# energia.net
KiCad netlist of a schematic drawn in EAGLE
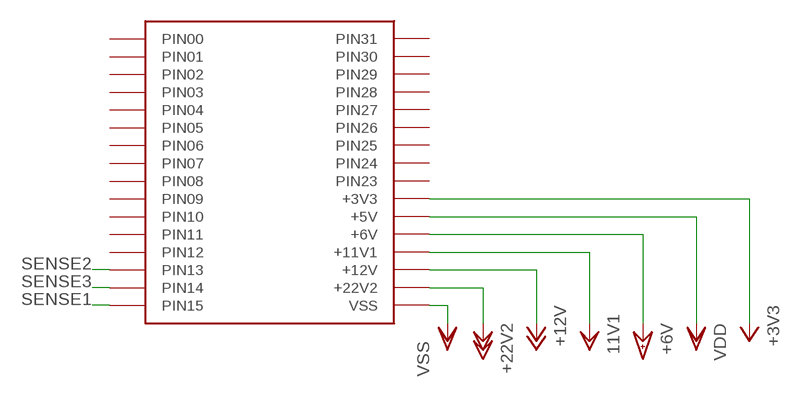
[diagram p0: schematic, sheet 1]
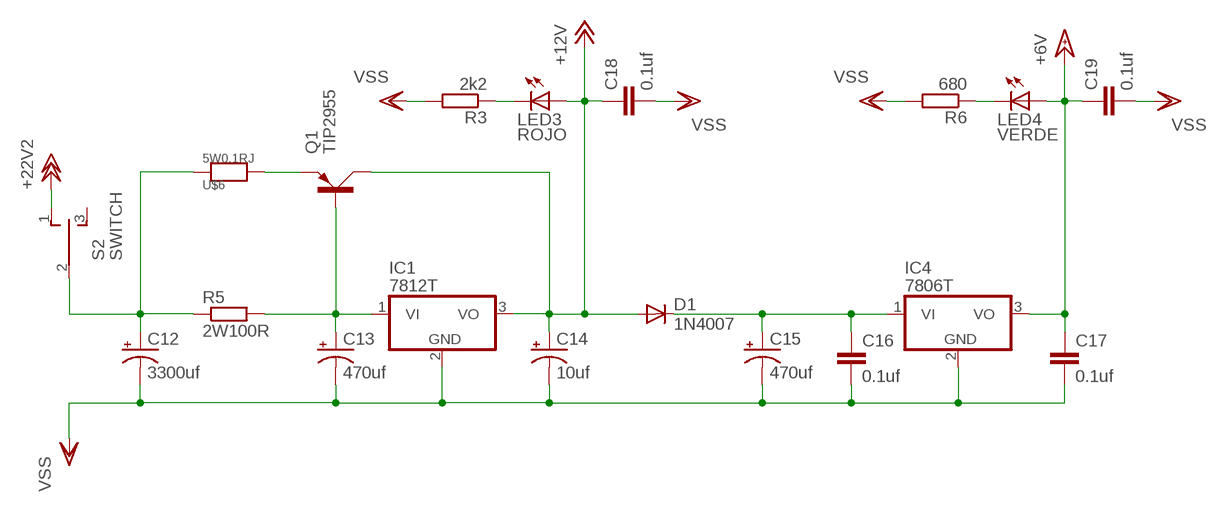
[diagram p1: schematic, sheet 2]
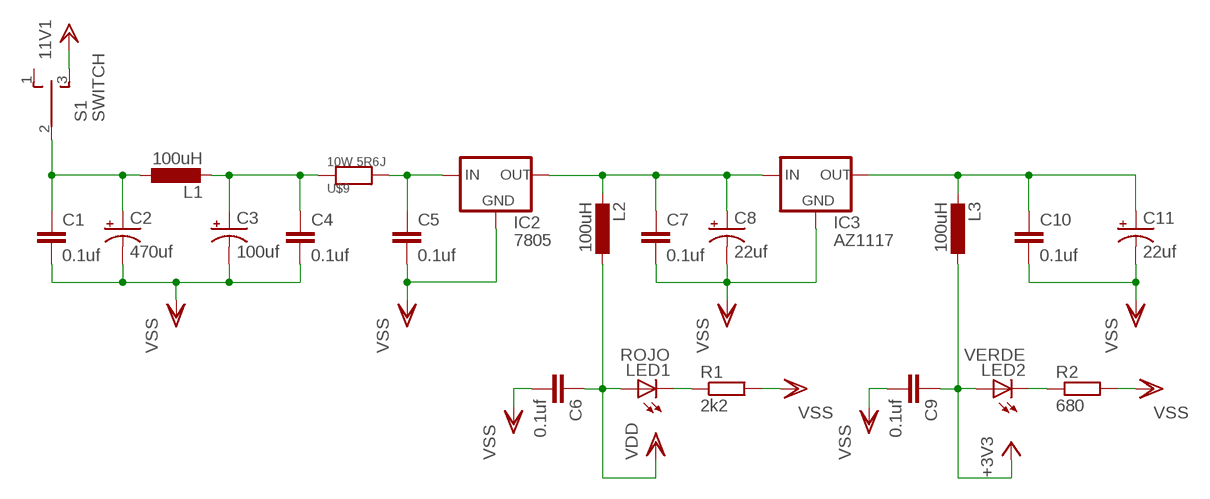
[diagram p2: schematic, sheet 3]
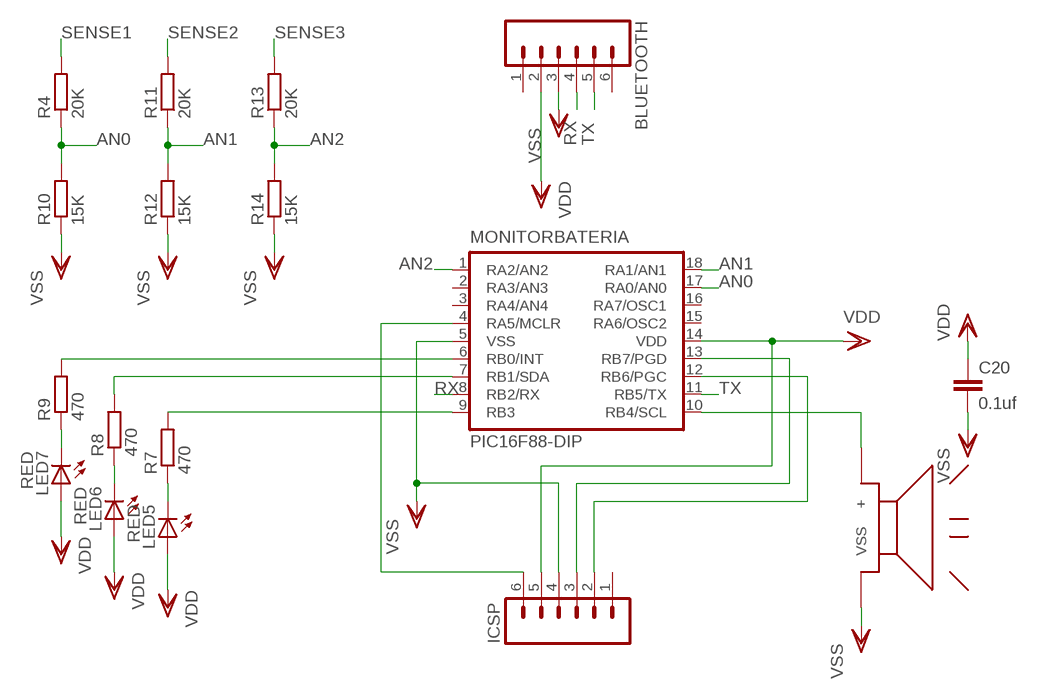
[diagram p3: schematic, sheet 4]

(export (version "E")
  (design (tool "Eeschema 10.0.6"))
  (components
    (comp (ref "BLUETOOTH")
      (value "M06LONGPADS")
      (footprint "eagle-import:1X06_LONGPADS")
      (libsource (lib "eagle-import") (part "M06LONGPADS"))
    )
    (comp (ref "C20")
      (value "0.1uf")
      (footprint "eagle-import:C050-024X044")
      (libsource (lib "eagle-import") (part "C-EU050-024X044"))
    )
    (comp (ref "ICSP")
      (value "M06LONGPADS")
      (footprint "eagle-import:1X06_LONGPADS")
      (libsource (lib "eagle-import") (part "M06LONGPADS"))
    )
    (comp (ref "LED5")
      (value "RED")
      (footprint "eagle-import:LED3MM")
      (libsource (lib "eagle-import") (part "LED3MM"))
    )
    (comp (ref "LED6")
      (value "RED")
      (footprint "eagle-import:LED3MM")
      (libsource (lib "eagle-import") (part "LED3MM"))
    )
    (comp (ref "LED7")
      (value "RED")
      (footprint "eagle-import:LED3MM")
      (libsource (lib "eagle-import") (part "LED3MM"))
    )
    (comp (ref "MONITORBATERIA")
      (value "PIC16F88-DIP")
      (footprint "eagle-import:DIL18")
      (libsource (lib "eagle-import") (part "PIC16F88-DIP"))
    )
    (comp (ref "R4")
      (value "20K")
      (footprint "eagle-import:0204_5")
      (libsource (lib "eagle-import") (part "R-EU_0204/5"))
    )
    (comp (ref "R7")
      (value "470")
      (footprint "eagle-import:0204_5")
      (libsource (lib "eagle-import") (part "R-EU_0204/5"))
    )
    (comp (ref "R8")
      (value "470")
      (footprint "eagle-import:0204_5")
      (libsource (lib "eagle-import") (part "R-EU_0204/5"))
    )
    (comp (ref "R9")
      (value "470")
      (footprint "eagle-import:0204_5")
      (libsource (lib "eagle-import") (part "R-EU_0204/5"))
    )
    (comp (ref "R10")
      (value "15K")
      (footprint "eagle-import:0204_5")
      (libsource (lib "eagle-import") (part "R-EU_0204/5"))
    )
    (comp (ref "R11")
      (value "20K")
      (footprint "eagle-import:0204_5")
      (libsource (lib "eagle-import") (part "R-EU_0204/5"))
    )
    (comp (ref "R12")
      (value "15K")
      (footprint "eagle-import:0204_5")
      (libsource (lib "eagle-import") (part "R-EU_0204/5"))
    )
    (comp (ref "R13")
      (value "20K")
      (footprint "eagle-import:0204_5")
      (libsource (lib "eagle-import") (part "R-EU_0204/5"))
    )
    (comp (ref "R14")
      (value "15K")
      (footprint "eagle-import:0204_5")
      (libsource (lib "eagle-import") (part "R-EU_0204/5"))
    )
    (comp (ref "U$10")
      (value "BUZZER")
      (footprint "eagle-import:BUZZER")
      (libsource (lib "eagle-import") (part "BUZZER"))
    )
    (comp (ref "C12")
      (value "3300uf")
      (footprint "eagle-import:E7,5-18")
      (libsource (lib "eagle-import") (part "CPOL-USE7.5-18"))
    )
    (comp (ref "C13")
      (value "470uf")
      (footprint "eagle-import:E3,5-8")
      (libsource (lib "eagle-import") (part "CPOL-USE3.5-8"))
    )
    (comp (ref "C14")
      (value "10uf")
      (footprint "eagle-import:E2,5-5")
      (libsource (lib "eagle-import") (part "CPOL-USE2.5-5"))
    )
    (comp (ref "C15")
      (value "470uf")
      (footprint "eagle-import:E3,5-8")
      (libsource (lib "eagle-import") (part "CPOL-USE3.5-8"))
    )
    (comp (ref "C16")
      (value "0.1uf")
      (footprint "eagle-import:C050-024X044")
      (libsource (lib "eagle-import") (part "C-EU050-024X044"))
    )
    (comp (ref "C17")
      (value "0.1uf")
      (footprint "eagle-import:C050-024X044")
      (libsource (lib "eagle-import") (part "C-EU050-024X044"))
    )
    (comp (ref "C18")
      (value "0.1uf")
      (footprint "eagle-import:C050-024X044")
      (libsource (lib "eagle-import") (part "C-EU050-024X044"))
    )
    (comp (ref "C19")
      (value "0.1uf")
      (footprint "eagle-import:C050-024X044")
      (libsource (lib "eagle-import") (part "C-EU050-024X044"))
    )
    (comp (ref "D1")
      (value "1N4007")
      (footprint "eagle-import:DO41-10")
      (libsource (lib "eagle-import") (part "1N4004"))
    )
    (comp (ref "IC1")
      (value "7812T")
      (footprint "eagle-import:TO220H")
      (libsource (lib "eagle-import") (part "78T12"))
    )
    (comp (ref "IC4")
      (value "7806T")
      (footprint "eagle-import:TO220H")
      (libsource (lib "eagle-import") (part "78T06"))
    )
    (comp (ref "LED3")
      (value "ROJO")
      (footprint "eagle-import:LED3MM")
      (libsource (lib "eagle-import") (part "LED3MM"))
    )
    (comp (ref "LED4")
      (value "VERDE")
      (footprint "eagle-import:LED3MM")
      (libsource (lib "eagle-import") (part "LED3MM"))
    )
    (comp (ref "Q1")
      (value "TIP2955")
      (footprint "eagle-import:TOP3AV")
      (libsource (lib "eagle-import") (part "TIP2955"))
    )
    (comp (ref "R3")
      (value "2k2")
      (footprint "eagle-import:0204_5")
      (libsource (lib "eagle-import") (part "R-EU_0204/5"))
    )
    (comp (ref "R5")
      (value "2W100R")
      (footprint "eagle-import:0411_12")
      (libsource (lib "eagle-import") (part "R-EU_0411/12"))
    )
    (comp (ref "R6")
      (value "680")
      (footprint "eagle-import:0204_5")
      (libsource (lib "eagle-import") (part "R-EU_0204/5"))
    )
    (comp (ref "S2")
      (value "SWITCH")
      (footprint "eagle-import:TL3XYO")
      (libsource (lib "eagle-import") (part "TL39YOSWITCH_2_ESTADOS"))
    )
    (comp (ref "U$6")
      (value "5W0.1RJ")
      (footprint "eagle-import:RES-22X10")
      (libsource (lib "eagle-import") (part "RESISTENCIA5WATT"))
    )
    (comp (ref "C1")
      (value "0.1uf")
      (footprint "eagle-import:C050-024X044")
      (libsource (lib "eagle-import") (part "C-EU050-024X044"))
    )
    (comp (ref "C2")
      (value "470uf")
      (footprint "eagle-import:E2,5-7")
      (libsource (lib "eagle-import") (part "CPOL-USE2.5-7"))
    )
    (comp (ref "C3")
      (value "100uf")
      (footprint "eagle-import:E2,5-7")
      (libsource (lib "eagle-import") (part "CPOL-USE2.5-7"))
    )
    (comp (ref "C4")
      (value "0.1uf")
      (footprint "eagle-import:C050-024X044")
      (libsource (lib "eagle-import") (part "C-EU050-024X044"))
    )
    (comp (ref "C5")
      (value "0.1uf")
      (footprint "eagle-import:C050-024X044")
      (libsource (lib "eagle-import") (part "C-EU050-024X044"))
    )
    (comp (ref "C6")
      (value "0.1uf")
      (footprint "eagle-import:C050-024X044")
      (libsource (lib "eagle-import") (part "C-EU050-024X044"))
    )
    (comp (ref "C7")
      (value "0.1uf")
      (footprint "eagle-import:C050-024X044")
      (libsource (lib "eagle-import") (part "C-EU050-024X044"))
    )
    (comp (ref "C8")
      (value "22uf")
      (footprint "eagle-import:E2,5-7")
      (libsource (lib "eagle-import") (part "CPOL-USE2.5-7"))
    )
    (comp (ref "C9")
      (value "0.1uf")
      (footprint "eagle-import:C050-024X044")
      (libsource (lib "eagle-import") (part "C-EU050-024X044"))
    )
    (comp (ref "C10")
      (value "0.1uf")
      (footprint "eagle-import:C050-024X044")
      (libsource (lib "eagle-import") (part "C-EU050-024X044"))
    )
    (comp (ref "C11")
      (value "22uf")
      (footprint "eagle-import:E2,5-7")
      (libsource (lib "eagle-import") (part "CPOL-USE2.5-7"))
    )
    (comp (ref "IC2")
      (value "7805")
      (footprint "eagle-import:TO-220-ALT")
      (libsource (lib "eagle-import") (part "V_REG_78XX-TO-220"))
    )
    (comp (ref "IC3")
      (value "AZ1117")
      (footprint "eagle-import:78XXL")
      (libsource (lib "eagle-import") (part "V_REG_LD1117VXX"))
    )
    (comp (ref "L1")
      (value "100uH")
      (footprint "eagle-import:TFI0307")
      (libsource (lib "eagle-import") (part "L-EUTFI0307"))
    )
    (comp (ref "L2")
      (value "100uH")
      (footprint "eagle-import:0207_7")
      (libsource (lib "eagle-import") (part "L-EU0207/7"))
    )
    (comp (ref "L3")
      (value "100uH")
      (footprint "eagle-import:0207_7")
      (libsource (lib "eagle-import") (part "L-EU0207/7"))
    )
    (comp (ref "LED1")
      (value "ROJO")
      (footprint "eagle-import:LED3MM")
      (libsource (lib "eagle-import") (part "LED3MM"))
    )
    (comp (ref "LED2")
      (value "VERDE")
      (footprint "eagle-import:LED3MM")
      (libsource (lib "eagle-import") (part "LED3MM"))
    )
    (comp (ref "R1")
      (value "2k2")
      (footprint "eagle-import:0204_5")
      (libsource (lib "eagle-import") (part "R-EU_0204/5"))
    )
    (comp (ref "R2")
      (value "680")
      (footprint "eagle-import:0204_5")
      (libsource (lib "eagle-import") (part "R-EU_0204/5"))
    )
    (comp (ref "S1")
      (value "SWITCH")
      (footprint "eagle-import:TL3XYO")
      (libsource (lib "eagle-import") (part "TL39YOSWITCH_2_ESTADOS"))
    )
    (comp (ref "U$9")
      (value "10W 5R6J")
      (footprint "eagle-import:RES-49X10")
      (libsource (lib "eagle-import") (part "RESISTENCIA10W"))
    )
    (comp (ref "U$1")
      (value "BASE")
      (footprint "eagle-import:BASE")
      (libsource (lib "eagle-import") (part "BASE"))
    )
  )
  (nets
    (net (code "1") (name "+3V3") (class "Default")
      (node (ref "C9") (pin "1") (pinfunction "1_1") (pintype "passive"))
      (node (ref "L3") (pin "1") (pinfunction "1_1") (pintype "passive"))
      (node (ref "LED2") (pin "A") (pinfunction "A_A") (pintype "passive"))
      (node (ref "U$1") (pin "PIN22") (pinfunction "+3V3_PIN22") (pintype "bidirectional"))
    )
    (net (code "2") (name "+6V") (class "Default")
      (node (ref "C17") (pin "1") (pinfunction "1_1") (pintype "passive"))
      (node (ref "C19") (pin "1") (pinfunction "1_1") (pintype "passive"))
      (node (ref "IC4") (pin "3") (pinfunction "VO_3") (pintype "passive"))
      (node (ref "LED4") (pin "A") (pinfunction "A_A") (pintype "passive"))
      (node (ref "U$1") (pin "PIN20") (pinfunction "+6V_PIN20") (pintype "bidirectional"))
    )
    (net (code "3") (name "+11V1") (class "Default")
      (node (ref "S1") (pin "3") (pinfunction "S_3") (pintype "passive"))
      (node (ref "U$1") (pin "PIN19") (pinfunction "+11V1_PIN19") (pintype "bidirectional"))
    )
    (net (code "4") (name "+12V") (class "Default")
      (node (ref "C14") (pin "+") (pinfunction "+_+") (pintype "passive"))
      (node (ref "C18") (pin "1") (pinfunction "1_1") (pintype "passive"))
      (node (ref "D1") (pin "A") (pinfunction "A_A") (pintype "passive"))
      (node (ref "IC1") (pin "3") (pinfunction "VO_3") (pintype "passive"))
      (node (ref "LED3") (pin "A") (pinfunction "A_A") (pintype "passive"))
      (node (ref "Q1") (pin "C") (pinfunction "C_C") (pintype "passive"))
      (node (ref "U$1") (pin "PIN18") (pinfunction "+12V_PIN18") (pintype "bidirectional"))
    )
    (net (code "5") (name "+22V") (class "Default")
      (node (ref "S2") (pin "1") (pinfunction "O_1") (pintype "passive"))
      (node (ref "U$1") (pin "PIN17") (pinfunction "+22V2_PIN17") (pintype "bidirectional"))
    )
    (net (code "6") (name "AN0") (class "Default")
      (node (ref "MONITORBATERIA") (pin "17") (pinfunction "RA0/AN0_17") (pintype "bidirectional"))
      (node (ref "R10") (pin "2") (pinfunction "2_2") (pintype "passive"))
      (node (ref "R4") (pin "1") (pinfunction "1_1") (pintype "passive"))
    )
    (net (code "7") (name "AN1") (class "Default")
      (node (ref "MONITORBATERIA") (pin "18") (pinfunction "RA1/AN1_18") (pintype "bidirectional"))
      (node (ref "R11") (pin "1") (pinfunction "1_1") (pintype "passive"))
      (node (ref "R12") (pin "2") (pinfunction "2_2") (pintype "passive"))
    )
    (net (code "8") (name "AN2") (class "Default")
      (node (ref "MONITORBATERIA") (pin "1") (pinfunction "RA2/AN2_1") (pintype "bidirectional"))
      (node (ref "R13") (pin "1") (pinfunction "1_1") (pintype "passive"))
      (node (ref "R14") (pin "2") (pinfunction "2_2") (pintype "passive"))
    )
    (net (code "9") (name "Net-(C3-Pad+)") (class "Default")
      (node (ref "C3") (pin "+") (pinfunction "+_+") (pintype "passive"))
      (node (ref "C4") (pin "1") (pinfunction "1_1") (pintype "passive"))
      (node (ref "L1") (pin "2") (pinfunction "2_2") (pintype "passive"))
      (node (ref "U$9") (pin "P$1") (pinfunction "P$1_P$1") (pintype "bidirectional"))
    )
    (net (code "10") (name "Net-(C5-Pad1)") (class "Default")
      (node (ref "C5") (pin "1") (pinfunction "1_1") (pintype "passive"))
      (node (ref "IC2") (pin "IN") (pinfunction "IN_IN") (pintype "input"))
      (node (ref "U$9") (pin "P$2") (pinfunction "P$2_P$2") (pintype "bidirectional"))
    )
    (net (code "11") (name "Net-(IC1-VI)") (class "Default")
      (node (ref "C13") (pin "+") (pinfunction "+_+") (pintype "passive"))
      (node (ref "IC1") (pin "1") (pinfunction "VI_1") (pintype "input"))
      (node (ref "Q1") (pin "B") (pinfunction "B_B") (pintype "passive"))
      (node (ref "R5") (pin "2") (pinfunction "2_2") (pintype "passive"))
    )
    (net (code "12") (name "Net-(IC3-IN)") (class "Default")
      (node (ref "C7") (pin "1") (pinfunction "1_1") (pintype "passive"))
      (node (ref "C8") (pin "+") (pinfunction "+_+") (pintype "passive"))
      (node (ref "IC2") (pin "OUT") (pinfunction "OUT_OUT") (pintype "output"))
      (node (ref "IC3") (pin "OUT") (pinfunction "IN_OUT") (pintype "input"))
      (node (ref "L2") (pin "2") (pinfunction "2_2") (pintype "passive"))
    )
    (net (code "13") (name "Net-(IC3-OUT)") (class "Default")
      (node (ref "C10") (pin "1") (pinfunction "1_1") (pintype "passive"))
      (node (ref "C11") (pin "+") (pinfunction "+_+") (pintype "passive"))
      (node (ref "IC3") (pin "GND") (pinfunction "OUT_GND") (pintype "output"))
      (node (ref "L3") (pin "2") (pinfunction "2_2") (pintype "passive"))
    )
    (net (code "14") (name "Net-(IC4-VI)") (class "Default")
      (node (ref "C15") (pin "+") (pinfunction "+_+") (pintype "passive"))
      (node (ref "C16") (pin "1") (pinfunction "1_1") (pintype "passive"))
      (node (ref "D1") (pin "C") (pinfunction "C_C") (pintype "passive"))
      (node (ref "IC4") (pin "1") (pinfunction "VI_1") (pintype "input"))
    )
    (net (code "15") (name "Net-(LED1-C)") (class "Default")
      (node (ref "LED1") (pin "K") (pinfunction "C_K") (pintype "passive"))
      (node (ref "R1") (pin "1") (pinfunction "1_1") (pintype "passive"))
    )
    (net (code "16") (name "Net-(LED2-C)") (class "Default")
      (node (ref "LED2") (pin "K") (pinfunction "C_K") (pintype "passive"))
      (node (ref "R2") (pin "1") (pinfunction "1_1") (pintype "passive"))
    )
    (net (code "17") (name "Net-(LED3-C)") (class "Default")
      (node (ref "LED3") (pin "K") (pinfunction "C_K") (pintype "passive"))
      (node (ref "R3") (pin "1") (pinfunction "1_1") (pintype "passive"))
    )
    (net (code "18") (name "Net-(LED4-C)") (class "Default")
      (node (ref "LED4") (pin "K") (pinfunction "C_K") (pintype "passive"))
      (node (ref "R6") (pin "1") (pinfunction "1_1") (pintype "passive"))
    )
    (net (code "19") (name "Net-(LED5-C)") (class "Default")
      (node (ref "LED5") (pin "K") (pinfunction "C_K") (pintype "passive"))
      (node (ref "R7") (pin "1") (pinfunction "1_1") (pintype "passive"))
    )
    (net (code "20") (name "Net-(LED6-C)") (class "Default")
      (node (ref "LED6") (pin "K") (pinfunction "C_K") (pintype "passive"))
      (node (ref "R8") (pin "1") (pinfunction "1_1") (pintype "passive"))
    )
    (net (code "21") (name "Net-(LED7-C)") (class "Default")
      (node (ref "LED7") (pin "K") (pinfunction "C_K") (pintype "passive"))
      (node (ref "R9") (pin "1") (pinfunction "1_1") (pintype "passive"))
    )
    (net (code "22") (name "Net-(MONITORBATERIA-RA5{slash}MCLR)") (class "Default")
      (node (ref "ICSP") (pin "6") (pinfunction "6_6") (pintype "passive"))
      (node (ref "MONITORBATERIA") (pin "4") (pinfunction "RA5/MCLR_4") (pintype "input"))
    )
    (net (code "23") (name "Net-(MONITORBATERIA-RB0{slash}INT)") (class "Default")
      (node (ref "MONITORBATERIA") (pin "6") (pinfunction "RB0/INT_6") (pintype "bidirectional"))
      (node (ref "R9") (pin "2") (pinfunction "2_2") (pintype "passive"))
    )
    (net (code "24") (name "Net-(MONITORBATERIA-RB1{slash}SDA)") (class "Default")
      (node (ref "MONITORBATERIA") (pin "7") (pinfunction "RB1/SDA_7") (pintype "bidirectional"))
      (node (ref "R8") (pin "2") (pinfunction "2_2") (pintype "passive"))
    )
    (net (code "25") (name "Net-(MONITORBATERIA-RB3)") (class "Default")
      (node (ref "MONITORBATERIA") (pin "9") (pinfunction "RB3_9") (pintype "bidirectional"))
      (node (ref "R7") (pin "2") (pinfunction "2_2") (pintype "passive"))
    )
    (net (code "26") (name "Net-(MONITORBATERIA-RB4{slash}SCL)") (class "Default")
      (node (ref "MONITORBATERIA") (pin "10") (pinfunction "RB4/SCL_10") (pintype "bidirectional"))
      (node (ref "U$10") (pin "+") (pinfunction "+_+") (pintype "bidirectional"))
    )
    (net (code "27") (name "Net-(MONITORBATERIA-RB6{slash}PGC)") (class "Default")
      (node (ref "ICSP") (pin "2") (pinfunction "2_2") (pintype "passive"))
      (node (ref "MONITORBATERIA") (pin "12") (pinfunction "RB6/PGC_12") (pintype "bidirectional"))
    )
    (net (code "28") (name "Net-(MONITORBATERIA-RB7{slash}PGD)") (class "Default")
      (node (ref "ICSP") (pin "3") (pinfunction "3_3") (pintype "passive"))
      (node (ref "MONITORBATERIA") (pin "13") (pinfunction "RB7/PGD_13") (pintype "bidirectional"))
    )
    (net (code "29") (name "Net-(Q1-PadE)") (class "Default")
      (node (ref "Q1") (pin "E") (pinfunction "E_E") (pintype "passive"))
      (node (ref "U$6") (pin "P$2") (pinfunction "P$2_P$2") (pintype "bidirectional"))
    )
    (net (code "30") (name "Net-(S1-P)") (class "Default")
      (node (ref "C1") (pin "1") (pinfunction "1_1") (pintype "passive"))
      (node (ref "C2") (pin "+") (pinfunction "+_+") (pintype "passive"))
      (node (ref "L1") (pin "1") (pinfunction "1_1") (pintype "passive"))
      (node (ref "S1") (pin "2") (pinfunction "P_2") (pintype "passive"))
    )
    (net (code "31") (name "Net-(S2-P)") (class "Default")
      (node (ref "C12") (pin "+") (pinfunction "+_+") (pintype "passive"))
      (node (ref "R5") (pin "1") (pinfunction "1_1") (pintype "passive"))
      (node (ref "S2") (pin "2") (pinfunction "P_2") (pintype "passive"))
      (node (ref "U$6") (pin "P$1") (pinfunction "P$1_P$1") (pintype "bidirectional"))
    )
    (net (code "32") (name "RX") (class "Default")
      (node (ref "BLUETOOTH") (pin "4") (pinfunction "4_4") (pintype "passive"))
      (node (ref "MONITORBATERIA") (pin "8") (pinfunction "RB2/RX_8") (pintype "bidirectional"))
    )
    (net (code "33") (name "SENSE1") (class "Default")
      (node (ref "R4") (pin "2") (pinfunction "2_2") (pintype "passive"))
      (node (ref "U$1") (pin "PIN15") (pinfunction "PIN15_PIN15") (pintype "bidirectional"))
    )
    (net (code "34") (name "SENSE2") (class "Default")
      (node (ref "R11") (pin "2") (pinfunction "2_2") (pintype "passive"))
      (node (ref "U$1") (pin "PIN13") (pinfunction "PIN13_PIN13") (pintype "bidirectional"))
    )
    (net (code "35") (name "SENSE3") (class "Default")
      (node (ref "R13") (pin "2") (pinfunction "2_2") (pintype "passive"))
      (node (ref "U$1") (pin "PIN14") (pinfunction "PIN14_PIN14") (pintype "bidirectional"))
    )
    (net (code "36") (name "TX") (class "Default")
      (node (ref "BLUETOOTH") (pin "5") (pinfunction "5_5") (pintype "passive"))
      (node (ref "MONITORBATERIA") (pin "11") (pinfunction "RB5/TX_11") (pintype "bidirectional"))
    )
    (net (code "37") (name "VDD") (class "Default")
      (node (ref "BLUETOOTH") (pin "2") (pinfunction "2_2") (pintype "passive"))
      (node (ref "C20") (pin "1") (pinfunction "1_1") (pintype "passive"))
      (node (ref "C6") (pin "1") (pinfunction "1_1") (pintype "passive"))
      (node (ref "ICSP") (pin "5") (pinfunction "5_5") (pintype "passive"))
      (node (ref "L2") (pin "1") (pinfunction "1_1") (pintype "passive"))
      (node (ref "LED1") (pin "A") (pinfunction "A_A") (pintype "passive"))
      (node (ref "LED5") (pin "A") (pinfunction "A_A") (pintype "passive"))
      (node (ref "LED6") (pin "A") (pinfunction "A_A") (pintype "passive"))
      (node (ref "LED7") (pin "A") (pinfunction "A_A") (pintype "passive"))
      (node (ref "MONITORBATERIA") (pin "14") (pinfunction "VDD_14") (pintype "power_in"))
      (node (ref "U$1") (pin "PIN21") (pinfunction "+5V_PIN21") (pintype "bidirectional"))
    )
    (net (code "38") (name "VSS") (class "Default")
      (node (ref "BLUETOOTH") (pin "3") (pinfunction "3_3") (pintype "passive"))
      (node (ref "C1") (pin "2") (pinfunction "2_2") (pintype "passive"))
      (node (ref "C10") (pin "2") (pinfunction "2_2") (pintype "passive"))
      (node (ref "C11") (pin "-") (pinfunction "-_-") (pintype "passive"))
      (node (ref "C12") (pin "-") (pinfunction "-_-") (pintype "passive"))
      (node (ref "C13") (pin "-") (pinfunction "-_-") (pintype "passive"))
      (node (ref "C14") (pin "-") (pinfunction "-_-") (pintype "passive"))
      (node (ref "C15") (pin "-") (pinfunction "-_-") (pintype "passive"))
      (node (ref "C16") (pin "2") (pinfunction "2_2") (pintype "passive"))
      (node (ref "C17") (pin "2") (pinfunction "2_2") (pintype "passive"))
      (node (ref "C18") (pin "2") (pinfunction "2_2") (pintype "passive"))
      (node (ref "C19") (pin "2") (pinfunction "2_2") (pintype "passive"))
      (node (ref "C2") (pin "-") (pinfunction "-_-") (pintype "passive"))
      (node (ref "C20") (pin "2") (pinfunction "2_2") (pintype "passive"))
      (node (ref "C3") (pin "-") (pinfunction "-_-") (pintype "passive"))
      (node (ref "C4") (pin "2") (pinfunction "2_2") (pintype "passive"))
      (node (ref "C5") (pin "2") (pinfunction "2_2") (pintype "passive"))
      (node (ref "C6") (pin "2") (pinfunction "2_2") (pintype "passive"))
      (node (ref "C7") (pin "2") (pinfunction "2_2") (pintype "passive"))
      (node (ref "C8") (pin "-") (pinfunction "-_-") (pintype "passive"))
      (node (ref "C9") (pin "2") (pinfunction "2_2") (pintype "passive"))
      (node (ref "IC1") (pin "2") (pinfunction "GND_2") (pintype "passive"))
      (node (ref "IC2") (pin "GND") (pinfunction "GND_GND") (pintype "input"))
      (node (ref "IC3") (pin "IN") (pinfunction "GND_IN") (pintype "input"))
      (node (ref "IC4") (pin "2") (pinfunction "GND_2") (pintype "passive"))
      (node (ref "ICSP") (pin "4") (pinfunction "4_4") (pintype "passive"))
      (node (ref "MONITORBATERIA") (pin "5") (pinfunction "VSS_5") (pintype "power_in"))
      (node (ref "R1") (pin "2") (pinfunction "2_2") (pintype "passive"))
      (node (ref "R10") (pin "1") (pinfunction "1_1") (pintype "passive"))
      (node (ref "R12") (pin "1") (pinfunction "1_1") (pintype "passive"))
      (node (ref "R14") (pin "1") (pinfunction "1_1") (pintype "passive"))
      (node (ref "R2") (pin "2") (pinfunction "2_2") (pintype "passive"))
      (node (ref "R3") (pin "2") (pinfunction "2_2") (pintype "passive"))
      (node (ref "R6") (pin "2") (pinfunction "2_2") (pintype "passive"))
      (node (ref "U$1") (pin "PIN16") (pinfunction "VSS_PIN16") (pintype "bidirectional"))
      (node (ref "U$10") (pin "-") (pinfunction "VSS_-") (pintype "bidirectional"))
    )
    (net (code "39") (name "unconnected-(BLUETOOTH-Pad1)") (class "Default")
      (node (ref "BLUETOOTH") (pin "1") (pinfunction "1_1") (pintype "passive"))
    )
    (net (code "40") (name "unconnected-(BLUETOOTH-Pad6)") (class "Default")
      (node (ref "BLUETOOTH") (pin "6") (pinfunction "6_6") (pintype "passive"))
    )
    (net (code "41") (name "unconnected-(ICSP-Pad1)") (class "Default")
      (node (ref "ICSP") (pin "1") (pinfunction "1_1") (pintype "passive"))
    )
    (net (code "42") (name "unconnected-(MONITORBATERIA-RA3{slash}AN3-Pad2)") (class "Default")
      (node (ref "MONITORBATERIA") (pin "2") (pinfunction "RA3/AN3_2") (pintype "bidirectional"))
    )
    (net (code "43") (name "unconnected-(MONITORBATERIA-RA4{slash}AN4-Pad3)") (class "Default")
      (node (ref "MONITORBATERIA") (pin "3") (pinfunction "RA4/AN4_3") (pintype "bidirectional"))
    )
    (net (code "44") (name "unconnected-(MONITORBATERIA-RA6{slash}OSC2-Pad15)") (class "Default")
      (node (ref "MONITORBATERIA") (pin "15") (pinfunction "RA6/OSC2_15") (pintype "bidirectional"))
    )
    (net (code "45") (name "unconnected-(MONITORBATERIA-RA7{slash}OSC1-Pad16)") (class "Default")
      (node (ref "MONITORBATERIA") (pin "16") (pinfunction "RA7/OSC1_16") (pintype "bidirectional"))
    )
    (net (code "46") (name "unconnected-(S1-O-Pad1)") (class "Default")
      (node (ref "S1") (pin "1") (pinfunction "O_1") (pintype "passive"))
    )
    (net (code "47") (name "unconnected-(S2-S-Pad3)") (class "Default")
      (node (ref "S2") (pin "3") (pinfunction "S_3") (pintype "passive"))
    )
    (net (code "48") (name "unconnected-(U$1-PadPIN00)") (class "Default")
      (node (ref "U$1") (pin "PIN00") (pinfunction "PIN00_PIN00") (pintype "bidirectional"))
    )
    (net (code "49") (name "unconnected-(U$1-PadPIN01)") (class "Default")
      (node (ref "U$1") (pin "PIN01") (pinfunction "PIN01_PIN01") (pintype "bidirectional"))
    )
    (net (code "50") (name "unconnected-(U$1-PadPIN02)") (class "Default")
      (node (ref "U$1") (pin "PIN02") (pinfunction "PIN02_PIN02") (pintype "bidirectional"))
    )
    (net (code "51") (name "unconnected-(U$1-PadPIN03)") (class "Default")
      (node (ref "U$1") (pin "PIN03") (pinfunction "PIN03_PIN03") (pintype "bidirectional"))
    )
    (net (code "52") (name "unconnected-(U$1-PadPIN04)") (class "Default")
      (node (ref "U$1") (pin "PIN04") (pinfunction "PIN04_PIN04") (pintype "bidirectional"))
    )
    (net (code "53") (name "unconnected-(U$1-PadPIN05)") (class "Default")
      (node (ref "U$1") (pin "PIN05") (pinfunction "PIN05_PIN05") (pintype "bidirectional"))
    )
    (net (code "54") (name "unconnected-(U$1-PadPIN06)") (class "Default")
      (node (ref "U$1") (pin "PIN06") (pinfunction "PIN06_PIN06") (pintype "bidirectional"))
    )
    (net (code "55") (name "unconnected-(U$1-PadPIN07)") (class "Default")
      (node (ref "U$1") (pin "PIN07") (pinfunction "PIN07_PIN07") (pintype "bidirectional"))
    )
    (net (code "56") (name "unconnected-(U$1-PadPIN08)") (class "Default")
      (node (ref "U$1") (pin "PIN08") (pinfunction "PIN08_PIN08") (pintype "bidirectional"))
    )
    (net (code "57") (name "unconnected-(U$1-PadPIN09)") (class "Default")
      (node (ref "U$1") (pin "PIN09") (pinfunction "PIN09_PIN09") (pintype "bidirectional"))
    )
    (net (code "58") (name "unconnected-(U$1-PadPIN10)") (class "Default")
      (node (ref "U$1") (pin "PIN10") (pinfunction "PIN10_PIN10") (pintype "bidirectional"))
    )
    (net (code "59") (name "unconnected-(U$1-PadPIN11)") (class "Default")
      (node (ref "U$1") (pin "PIN11") (pinfunction "PIN11_PIN11") (pintype "bidirectional"))
    )
    (net (code "60") (name "unconnected-(U$1-PadPIN12)") (class "Default")
      (node (ref "U$1") (pin "PIN12") (pinfunction "PIN12_PIN12") (pintype "bidirectional"))
    )
    (net (code "61") (name "unconnected-(U$1-PadPIN23)") (class "Default")
      (node (ref "U$1") (pin "PIN23") (pinfunction "PIN23_PIN23") (pintype "bidirectional"))
    )
    (net (code "62") (name "unconnected-(U$1-PadPIN24)") (class "Default")
      (node (ref "U$1") (pin "PIN24") (pinfunction "PIN24_PIN24") (pintype "bidirectional"))
    )
    (net (code "63") (name "unconnected-(U$1-PadPIN25)") (class "Default")
      (node (ref "U$1") (pin "PIN25") (pinfunction "PIN25_PIN25") (pintype "bidirectional"))
    )
    (net (code "64") (name "unconnected-(U$1-PadPIN26)") (class "Default")
      (node (ref "U$1") (pin "PIN26") (pinfunction "PIN26_PIN26") (pintype "bidirectional"))
    )
    (net (code "65") (name "unconnected-(U$1-PadPIN27)") (class "Default")
      (node (ref "U$1") (pin "PIN27") (pinfunction "PIN27_PIN27") (pintype "bidirectional"))
    )
    (net (code "66") (name "unconnected-(U$1-PadPIN28)") (class "Default")
      (node (ref "U$1") (pin "PIN28") (pinfunction "PIN28_PIN28") (pintype "bidirectional"))
    )
    (net (code "67") (name "unconnected-(U$1-PadPIN29)") (class "Default")
      (node (ref "U$1") (pin "PIN29") (pinfunction "PIN29_PIN29") (pintype "bidirectional"))
    )
    (net (code "68") (name "unconnected-(U$1-PadPIN30)") (class "Default")
      (node (ref "U$1") (pin "PIN30") (pinfunction "PIN30_PIN30") (pintype "bidirectional"))
    )
    (net (code "69") (name "unconnected-(U$1-PadPIN31)") (class "Default")
      (node (ref "U$1") (pin "PIN31") (pinfunction "PIN31_PIN31") (pintype "bidirectional"))
    )
  )
)
